# Light_Control_-_6ports_Ext_Board.net
KiCad netlist of a schematic drawn in Altium Designer
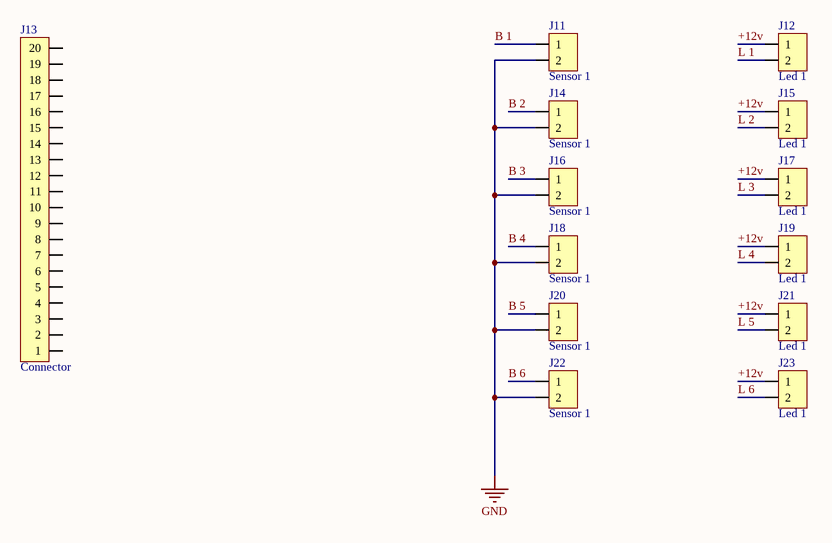
[diagram p0: Light Control - 6ports Ext Board.SchDoc]

(export (version "E")
  (design (tool "Eeschema 10.0.6"))
  (components
    (comp (ref "J11")
      (value "Sensor 1")
      (footprint "Connector:DG301 5mm 2p")
      (description "DG301 series")
      (libsource (lib "Connector") (part "DG301-5.0-2P12"))
    )
    (comp (ref "J12")
      (value "Led 1")
      (footprint "Connector:DG301 5mm 2p")
      (description "DG301 series")
      (libsource (lib "Connector") (part "DG301-5.0-2P12"))
    )
    (comp (ref "J13")
      (value "Connector")
      (footprint "Connector:LINE 2.54 x 20D (2 x 10) - BH")
      (description "Vert, Dbl line, Male")
      (libsource (lib "Connector") (part "PLD-20 (2 x 10)"))
    )
    (comp (ref "J14")
      (value "Sensor 1")
      (footprint "Connector:DG301 5mm 2p")
      (description "DG301 series")
      (libsource (lib "Connector") (part "DG301-5.0-2P12"))
    )
    (comp (ref "J15")
      (value "Led 1")
      (footprint "Connector:DG301 5mm 2p")
      (description "DG301 series")
      (libsource (lib "Connector") (part "DG301-5.0-2P12"))
    )
    (comp (ref "J16")
      (value "Sensor 1")
      (footprint "Connector:DG301 5mm 2p")
      (description "DG301 series")
      (libsource (lib "Connector") (part "DG301-5.0-2P12"))
    )
    (comp (ref "J17")
      (value "Led 1")
      (footprint "Connector:DG301 5mm 2p")
      (description "DG301 series")
      (libsource (lib "Connector") (part "DG301-5.0-2P12"))
    )
    (comp (ref "J18")
      (value "Sensor 1")
      (footprint "Connector:DG301 5mm 2p")
      (description "DG301 series")
      (libsource (lib "Connector") (part "DG301-5.0-2P12"))
    )
    (comp (ref "J19")
      (value "Led 1")
      (footprint "Connector:DG301 5mm 2p")
      (description "DG301 series")
      (libsource (lib "Connector") (part "DG301-5.0-2P12"))
    )
    (comp (ref "J20")
      (value "Sensor 1")
      (footprint "Connector:DG301 5mm 2p")
      (description "DG301 series")
      (libsource (lib "Connector") (part "DG301-5.0-2P12"))
    )
    (comp (ref "J21")
      (value "Led 1")
      (footprint "Connector:DG301 5mm 2p")
      (description "DG301 series")
      (libsource (lib "Connector") (part "DG301-5.0-2P12"))
    )
    (comp (ref "J22")
      (value "Sensor 1")
      (footprint "Connector:DG301 5mm 2p")
      (description "DG301 series")
      (libsource (lib "Connector") (part "DG301-5.0-2P12"))
    )
    (comp (ref "J23")
      (value "Led 1")
      (footprint "Connector:DG301 5mm 2p")
      (description "DG301 series")
      (libsource (lib "Connector") (part "DG301-5.0-2P12"))
    )
  )
  (nets
    (net (code "1") (name "/+12v") (class "Default")
      (node (ref "J12") (pin "1") (pinfunction "1_1") (pintype "passive"))
      (node (ref "J15") (pin "1") (pinfunction "1_1") (pintype "passive"))
      (node (ref "J17") (pin "1") (pinfunction "1_1") (pintype "passive"))
      (node (ref "J19") (pin "1") (pinfunction "1_1") (pintype "passive"))
      (node (ref "J21") (pin "1") (pinfunction "1_1") (pintype "passive"))
      (node (ref "J23") (pin "1") (pinfunction "1_1") (pintype "passive"))
    )
    (net (code "2") (name "/B 1") (class "Default")
      (node (ref "J11") (pin "1") (pinfunction "1_1") (pintype "passive"))
    )
    (net (code "3") (name "/B 2") (class "Default")
      (node (ref "J14") (pin "1") (pinfunction "1_1") (pintype "passive"))
    )
    (net (code "4") (name "/B 3") (class "Default")
      (node (ref "J16") (pin "1") (pinfunction "1_1") (pintype "passive"))
    )
    (net (code "5") (name "/B 4") (class "Default")
      (node (ref "J18") (pin "1") (pinfunction "1_1") (pintype "passive"))
    )
    (net (code "6") (name "/B 5") (class "Default")
      (node (ref "J20") (pin "1") (pinfunction "1_1") (pintype "passive"))
    )
    (net (code "7") (name "/B 6") (class "Default")
      (node (ref "J22") (pin "1") (pinfunction "1_1") (pintype "passive"))
    )
    (net (code "8") (name "/L 1") (class "Default")
      (node (ref "J12") (pin "2") (pinfunction "2_2") (pintype "passive"))
    )
    (net (code "9") (name "/L 2") (class "Default")
      (node (ref "J15") (pin "2") (pinfunction "2_2") (pintype "passive"))
    )
    (net (code "10") (name "/L 3") (class "Default")
      (node (ref "J17") (pin "2") (pinfunction "2_2") (pintype "passive"))
    )
    (net (code "11") (name "/L 4") (class "Default")
      (node (ref "J19") (pin "2") (pinfunction "2_2") (pintype "passive"))
    )
    (net (code "12") (name "/L 5") (class "Default")
      (node (ref "J21") (pin "2") (pinfunction "2_2") (pintype "passive"))
    )
    (net (code "13") (name "/L 6") (class "Default")
      (node (ref "J23") (pin "2") (pinfunction "2_2") (pintype "passive"))
    )
    (net (code "14") (name "GND") (class "Default")
      (node (ref "J11") (pin "2") (pinfunction "2_2") (pintype "passive"))
      (node (ref "J14") (pin "2") (pinfunction "2_2") (pintype "passive"))
      (node (ref "J16") (pin "2") (pinfunction "2_2") (pintype "passive"))
      (node (ref "J18") (pin "2") (pinfunction "2_2") (pintype "passive"))
      (node (ref "J20") (pin "2") (pinfunction "2_2") (pintype "passive"))
      (node (ref "J22") (pin "2") (pinfunction "2_2") (pintype "passive"))
    )
    (net (code "15") (name "unconnected-(J13-Pad1)") (class "Default")
      (node (ref "J13") (pin "1") (pinfunction "1_1") (pintype "passive"))
    )
    (net (code "16") (name "unconnected-(J13-Pad2)") (class "Default")
      (node (ref "J13") (pin "2") (pinfunction "2_2") (pintype "passive"))
    )
    (net (code "17") (name "unconnected-(J13-Pad3)") (class "Default")
      (node (ref "J13") (pin "3") (pinfunction "3_3") (pintype "passive"))
    )
    (net (code "18") (name "unconnected-(J13-Pad4)") (class "Default")
      (node (ref "J13") (pin "4") (pinfunction "4_4") (pintype "passive"))
    )
    (net (code "19") (name "unconnected-(J13-Pad5)") (class "Default")
      (node (ref "J13") (pin "5") (pinfunction "5_5") (pintype "passive"))
    )
    (net (code "20") (name "unconnected-(J13-Pad6)") (class "Default")
      (node (ref "J13") (pin "6") (pinfunction "6_6") (pintype "passive"))
    )
    (net (code "21") (name "unconnected-(J13-Pad7)") (class "Default")
      (node (ref "J13") (pin "7") (pinfunction "7_7") (pintype "passive"))
    )
    (net (code "22") (name "unconnected-(J13-Pad8)") (class "Default")
      (node (ref "J13") (pin "8") (pinfunction "8_8") (pintype "passive"))
    )
    (net (code "23") (name "unconnected-(J13-Pad9)") (class "Default")
      (node (ref "J13") (pin "9") (pinfunction "9_9") (pintype "passive"))
    )
    (net (code "24") (name "unconnected-(J13-Pad10)") (class "Default")
      (node (ref "J13") (pin "10") (pinfunction "10_10") (pintype "passive"))
    )
    (net (code "25") (name "unconnected-(J13-Pad11)") (class "Default")
      (node (ref "J13") (pin "11") (pinfunction "11_11") (pintype "passive"))
    )
    (net (code "26") (name "unconnected-(J13-Pad12)") (class "Default")
      (node (ref "J13") (pin "12") (pinfunction "12_12") (pintype "passive"))
    )
    (net (code "27") (name "unconnected-(J13-Pad13)") (class "Default")
      (node (ref "J13") (pin "13") (pinfunction "13_13") (pintype "passive"))
    )
    (net (code "28") (name "unconnected-(J13-Pad14)") (class "Default")
      (node (ref "J13") (pin "14") (pinfunction "14_14") (pintype "passive"))
    )
    (net (code "29") (name "unconnected-(J13-Pad15)") (class "Default")
      (node (ref "J13") (pin "15") (pinfunction "15_15") (pintype "passive"))
    )
    (net (code "30") (name "unconnected-(J13-Pad16)") (class "Default")
      (node (ref "J13") (pin "16") (pinfunction "16_16") (pintype "passive"))
    )
    (net (code "31") (name "unconnected-(J13-Pad17)") (class "Default")
      (node (ref "J13") (pin "17") (pinfunction "17_17") (pintype "passive"))
    )
    (net (code "32") (name "unconnected-(J13-Pad18)") (class "Default")
      (node (ref "J13") (pin "18") (pinfunction "18_18") (pintype "passive"))
    )
    (net (code "33") (name "unconnected-(J13-Pad19)") (class "Default")
      (node (ref "J13") (pin "19") (pinfunction "19_19") (pintype "passive"))
    )
    (net (code "34") (name "unconnected-(J13-Pad20)") (class "Default")
      (node (ref "J13") (pin "20") (pinfunction "20_20") (pintype "passive"))
    )
  )
)
